# Atmega328p-Rst-Rec.net
KiCad netlist of a schematic drawn in EAGLE
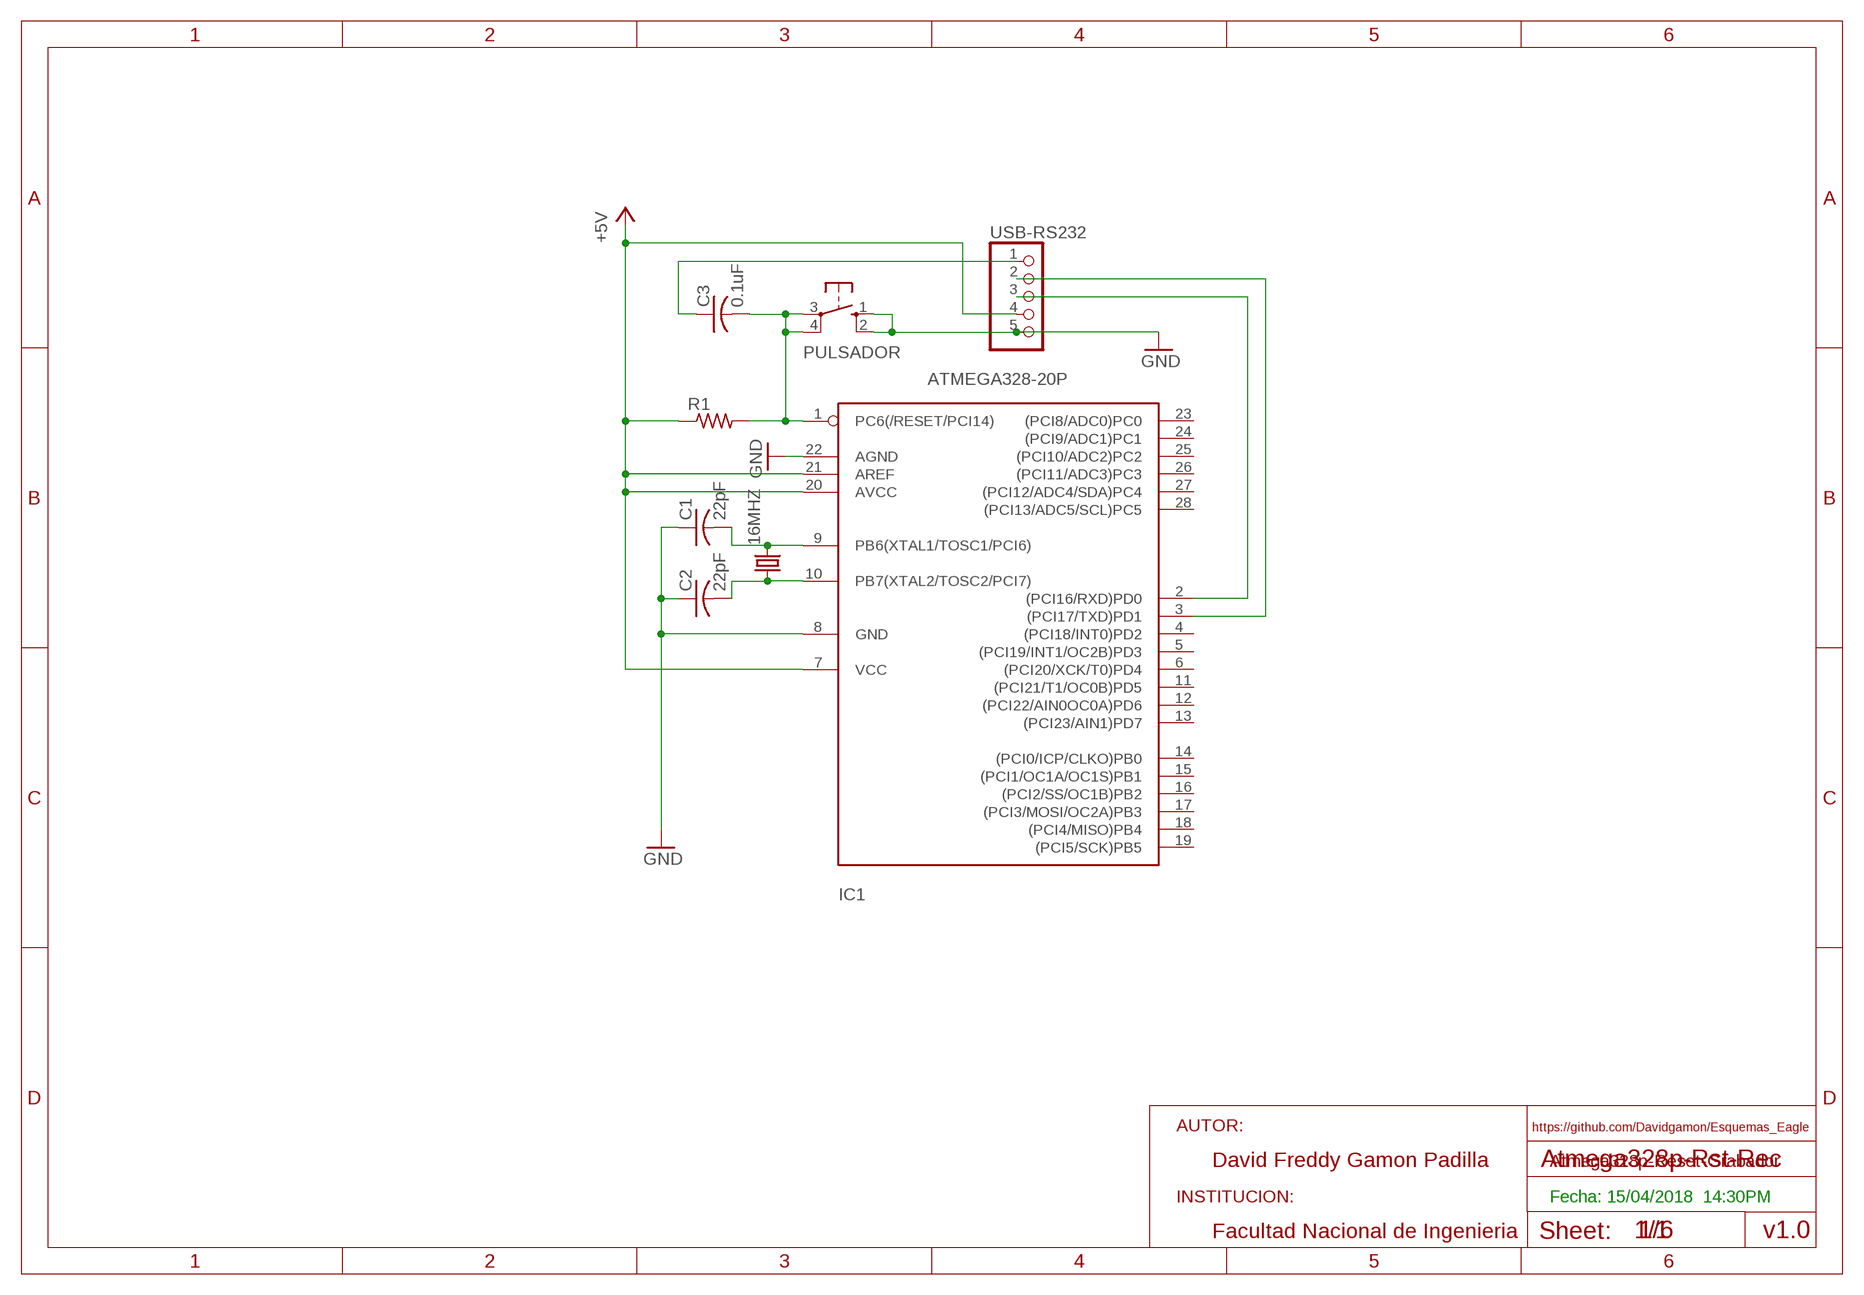
[diagram p0: schematic, sheet 1]

(export (version "E")
  (design (tool "Eeschema 10.0.6"))
  (components
    (comp (ref "16MHZ")
      (value "CRYSTALHC49S")
      (footprint "eagle-import:HC49_S")
      (libsource (lib "eagle-import") (part "CRYSTALHC49S"))
    )
    (comp (ref "C1")
      (value "22pF")
      (footprint "eagle-import:C025-030X050")
      (libsource (lib "eagle-import") (part "C-US025-030X050"))
    )
    (comp (ref "C2")
      (value "22pF")
      (footprint "eagle-import:C025-030X050")
      (libsource (lib "eagle-import") (part "C-US025-030X050"))
    )
    (comp (ref "C3")
      (value "0.1uF")
      (footprint "eagle-import:C025-030X050")
      (libsource (lib "eagle-import") (part "C-US025-030X050"))
    )
    (comp (ref "IC1")
      (value "ATMEGA328-20P")
      (footprint "eagle-import:DIL28-3")
      (libsource (lib "eagle-import") (part "ATMEGA328P-20"))
    )
    (comp (ref "PULSADOR")
      (value "10-XX")
      (footprint "eagle-import:B3F-10XX")
      (fields (field (name "MPN") "B3F-1000"))
      (libsource (lib "eagle-import") (part "10-XX"))
    )
    (comp (ref "R1")
      (value "R-US_0309/12")
      (footprint "eagle-import:0309_12")
      (libsource (lib "eagle-import") (part "R-US_0309/12"))
    )
    (comp (ref "USB-RS232")
      (value "PINHD-1X5")
      (footprint "eagle-import:1X05")
      (libsource (lib "eagle-import") (part "PINHD-1X5"))
    )
  )
  (nets
    (net (code "1") (name "+5V") (class "Default")
      (node (ref "IC1") (pin "20") (pinfunction "AVCC_20") (pintype "bidirectional"))
      (node (ref "IC1") (pin "21") (pinfunction "AREF_21") (pintype "bidirectional"))
      (node (ref "IC1") (pin "7") (pinfunction "VCC_7") (pintype "bidirectional"))
      (node (ref "R1") (pin "1") (pinfunction "1_1") (pintype "passive"))
      (node (ref "USB-RS232") (pin "4") (pinfunction "4_4") (pintype "passive"))
    )
    (net (code "2") (name "GND") (class "Default")
      (node (ref "C1") (pin "1") (pinfunction "1_1") (pintype "passive"))
      (node (ref "C2") (pin "1") (pinfunction "1_1") (pintype "passive"))
      (node (ref "IC1") (pin "22") (pinfunction "AGND_22") (pintype "bidirectional"))
      (node (ref "IC1") (pin "8") (pinfunction "GND_8") (pintype "bidirectional"))
      (node (ref "PULSADOR") (pin "1") (pinfunction "S_1") (pintype "passive"))
      (node (ref "PULSADOR") (pin "2") (pinfunction "S1_2") (pintype "passive"))
      (node (ref "USB-RS232") (pin "5") (pinfunction "5_5") (pintype "passive"))
    )
    (net (code "3") (name "Net-(C3-Pad1)") (class "Default")
      (node (ref "C3") (pin "1") (pinfunction "1_1") (pintype "passive"))
      (node (ref "USB-RS232") (pin "1") (pinfunction "1_1") (pintype "passive"))
    )
    (net (code "4") (name "Net-(IC1-(PCI16{slash}RXD)PD0)") (class "Default")
      (node (ref "IC1") (pin "2") (pinfunction "(PCI16/RXD)PD0_2") (pintype "bidirectional"))
      (node (ref "USB-RS232") (pin "3") (pinfunction "3_3") (pintype "passive"))
    )
    (net (code "5") (name "Net-(IC1-(PCI17{slash}TXD)PD1)") (class "Default")
      (node (ref "IC1") (pin "3") (pinfunction "(PCI17/TXD)PD1_3") (pintype "bidirectional"))
      (node (ref "USB-RS232") (pin "2") (pinfunction "2_2") (pintype "passive"))
    )
    (net (code "6") (name "Net-(IC1-PB6(XTAL1{slash}TOSC1{slash}PCI6))") (class "Default")
      (node (ref "16MHZ") (pin "2") (pinfunction "2_2") (pintype "passive"))
      (node (ref "C1") (pin "2") (pinfunction "2_2") (pintype "passive"))
      (node (ref "IC1") (pin "9") (pinfunction "PB6(XTAL1/TOSC1/PCI6)_9") (pintype "bidirectional"))
    )
    (net (code "7") (name "Net-(IC1-PB7(XTAL2{slash}TOSC2{slash}PCI7))") (class "Default")
      (node (ref "16MHZ") (pin "1") (pinfunction "1_1") (pintype "passive"))
      (node (ref "C2") (pin "2") (pinfunction "2_2") (pintype "passive"))
      (node (ref "IC1") (pin "10") (pinfunction "PB7(XTAL2/TOSC2/PCI7)_10") (pintype "bidirectional"))
    )
    (net (code "8") (name "Net-(IC1-PC6({slash}RESET{slash}PCI14))") (class "Default")
      (node (ref "C3") (pin "2") (pinfunction "2_2") (pintype "passive"))
      (node (ref "IC1") (pin "1") (pinfunction "PC6(/RESET/PCI14)_1") (pintype "bidirectional"))
      (node (ref "PULSADOR") (pin "3") (pinfunction "P_3") (pintype "passive"))
      (node (ref "PULSADOR") (pin "4") (pinfunction "P1_4") (pintype "passive"))
      (node (ref "R1") (pin "2") (pinfunction "2_2") (pintype "passive"))
    )
    (net (code "9") (name "unconnected-(IC1-(PCI0{slash}ICP{slash}CLKO)PB0-Pad14)") (class "Default")
      (node (ref "IC1") (pin "14") (pinfunction "(PCI0/ICP/CLKO)PB0_14") (pintype "bidirectional"))
    )
    (net (code "10") (name "unconnected-(IC1-(PCI1{slash}OC1A{slash}OC1S)PB1-Pad15)") (class "Default")
      (node (ref "IC1") (pin "15") (pinfunction "(PCI1/OC1A/OC1S)PB1_15") (pintype "bidirectional"))
    )
    (net (code "11") (name "unconnected-(IC1-(PCI2{slash}SS{slash}OC1B)PB2-Pad16)") (class "Default")
      (node (ref "IC1") (pin "16") (pinfunction "(PCI2/SS/OC1B)PB2_16") (pintype "bidirectional"))
    )
    (net (code "12") (name "unconnected-(IC1-(PCI3{slash}MOSI{slash}OC2A)PB3-Pad17)") (class "Default")
      (node (ref "IC1") (pin "17") (pinfunction "(PCI3/MOSI/OC2A)PB3_17") (pintype "bidirectional"))
    )
    (net (code "13") (name "unconnected-(IC1-(PCI4{slash}MISO)PB4-Pad18)") (class "Default")
      (node (ref "IC1") (pin "18") (pinfunction "(PCI4/MISO)PB4_18") (pintype "bidirectional"))
    )
    (net (code "14") (name "unconnected-(IC1-(PCI5{slash}SCK)PB5-Pad19)") (class "Default")
      (node (ref "IC1") (pin "19") (pinfunction "(PCI5/SCK)PB5_19") (pintype "bidirectional"))
    )
    (net (code "15") (name "unconnected-(IC1-(PCI8{slash}ADC0)PC0-Pad23)") (class "Default")
      (node (ref "IC1") (pin "23") (pinfunction "(PCI8/ADC0)PC0_23") (pintype "bidirectional"))
    )
    (net (code "16") (name "unconnected-(IC1-(PCI9{slash}ADC1)PC1-Pad24)") (class "Default")
      (node (ref "IC1") (pin "24") (pinfunction "(PCI9/ADC1)PC1_24") (pintype "bidirectional"))
    )
    (net (code "17") (name "unconnected-(IC1-(PCI10{slash}ADC2)PC2-Pad25)") (class "Default")
      (node (ref "IC1") (pin "25") (pinfunction "(PCI10/ADC2)PC2_25") (pintype "bidirectional"))
    )
    (net (code "18") (name "unconnected-(IC1-(PCI11{slash}ADC3)PC3-Pad26)") (class "Default")
      (node (ref "IC1") (pin "26") (pinfunction "(PCI11/ADC3)PC3_26") (pintype "bidirectional"))
    )
    (net (code "19") (name "unconnected-(IC1-(PCI12{slash}ADC4{slash}SDA)PC4-Pad27)") (class "Default")
      (node (ref "IC1") (pin "27") (pinfunction "(PCI12/ADC4/SDA)PC4_27") (pintype "bidirectional"))
    )
    (net (code "20") (name "unconnected-(IC1-(PCI13{slash}ADC5{slash}SCL)PC5-Pad28)") (class "Default")
      (node (ref "IC1") (pin "28") (pinfunction "(PCI13/ADC5/SCL)PC5_28") (pintype "bidirectional"))
    )
    (net (code "21") (name "unconnected-(IC1-(PCI18{slash}INT0)PD2-Pad4)") (class "Default")
      (node (ref "IC1") (pin "4") (pinfunction "(PCI18/INT0)PD2_4") (pintype "bidirectional"))
    )
    (net (code "22") (name "unconnected-(IC1-(PCI19{slash}INT1{slash}OC2B)PD3-Pad5)") (class "Default")
      (node (ref "IC1") (pin "5") (pinfunction "(PCI19/INT1/OC2B)PD3_5") (pintype "bidirectional"))
    )
    (net (code "23") (name "unconnected-(IC1-(PCI20{slash}XCK{slash}T0)PD4-Pad6)") (class "Default")
      (node (ref "IC1") (pin "6") (pinfunction "(PCI20/XCK/T0)PD4_6") (pintype "bidirectional"))
    )
    (net (code "24") (name "unconnected-(IC1-(PCI21{slash}T1{slash}OC0B)PD5-Pad11)") (class "Default")
      (node (ref "IC1") (pin "11") (pinfunction "(PCI21/T1/OC0B)PD5_11") (pintype "bidirectional"))
    )
    (net (code "25") (name "unconnected-(IC1-(PCI22{slash}AIN0OC0A)PD6-Pad12)") (class "Default")
      (node (ref "IC1") (pin "12") (pinfunction "(PCI22/AIN0OC0A)PD6_12") (pintype "bidirectional"))
    )
    (net (code "26") (name "unconnected-(IC1-(PCI23{slash}AIN1)PD7-Pad13)") (class "Default")
      (node (ref "IC1") (pin "13") (pinfunction "(PCI23/AIN1)PD7_13") (pintype "bidirectional"))
    )
  )
)
